# easyeda_schematic.net
KiCad netlist of a schematic drawn in EasyEDA
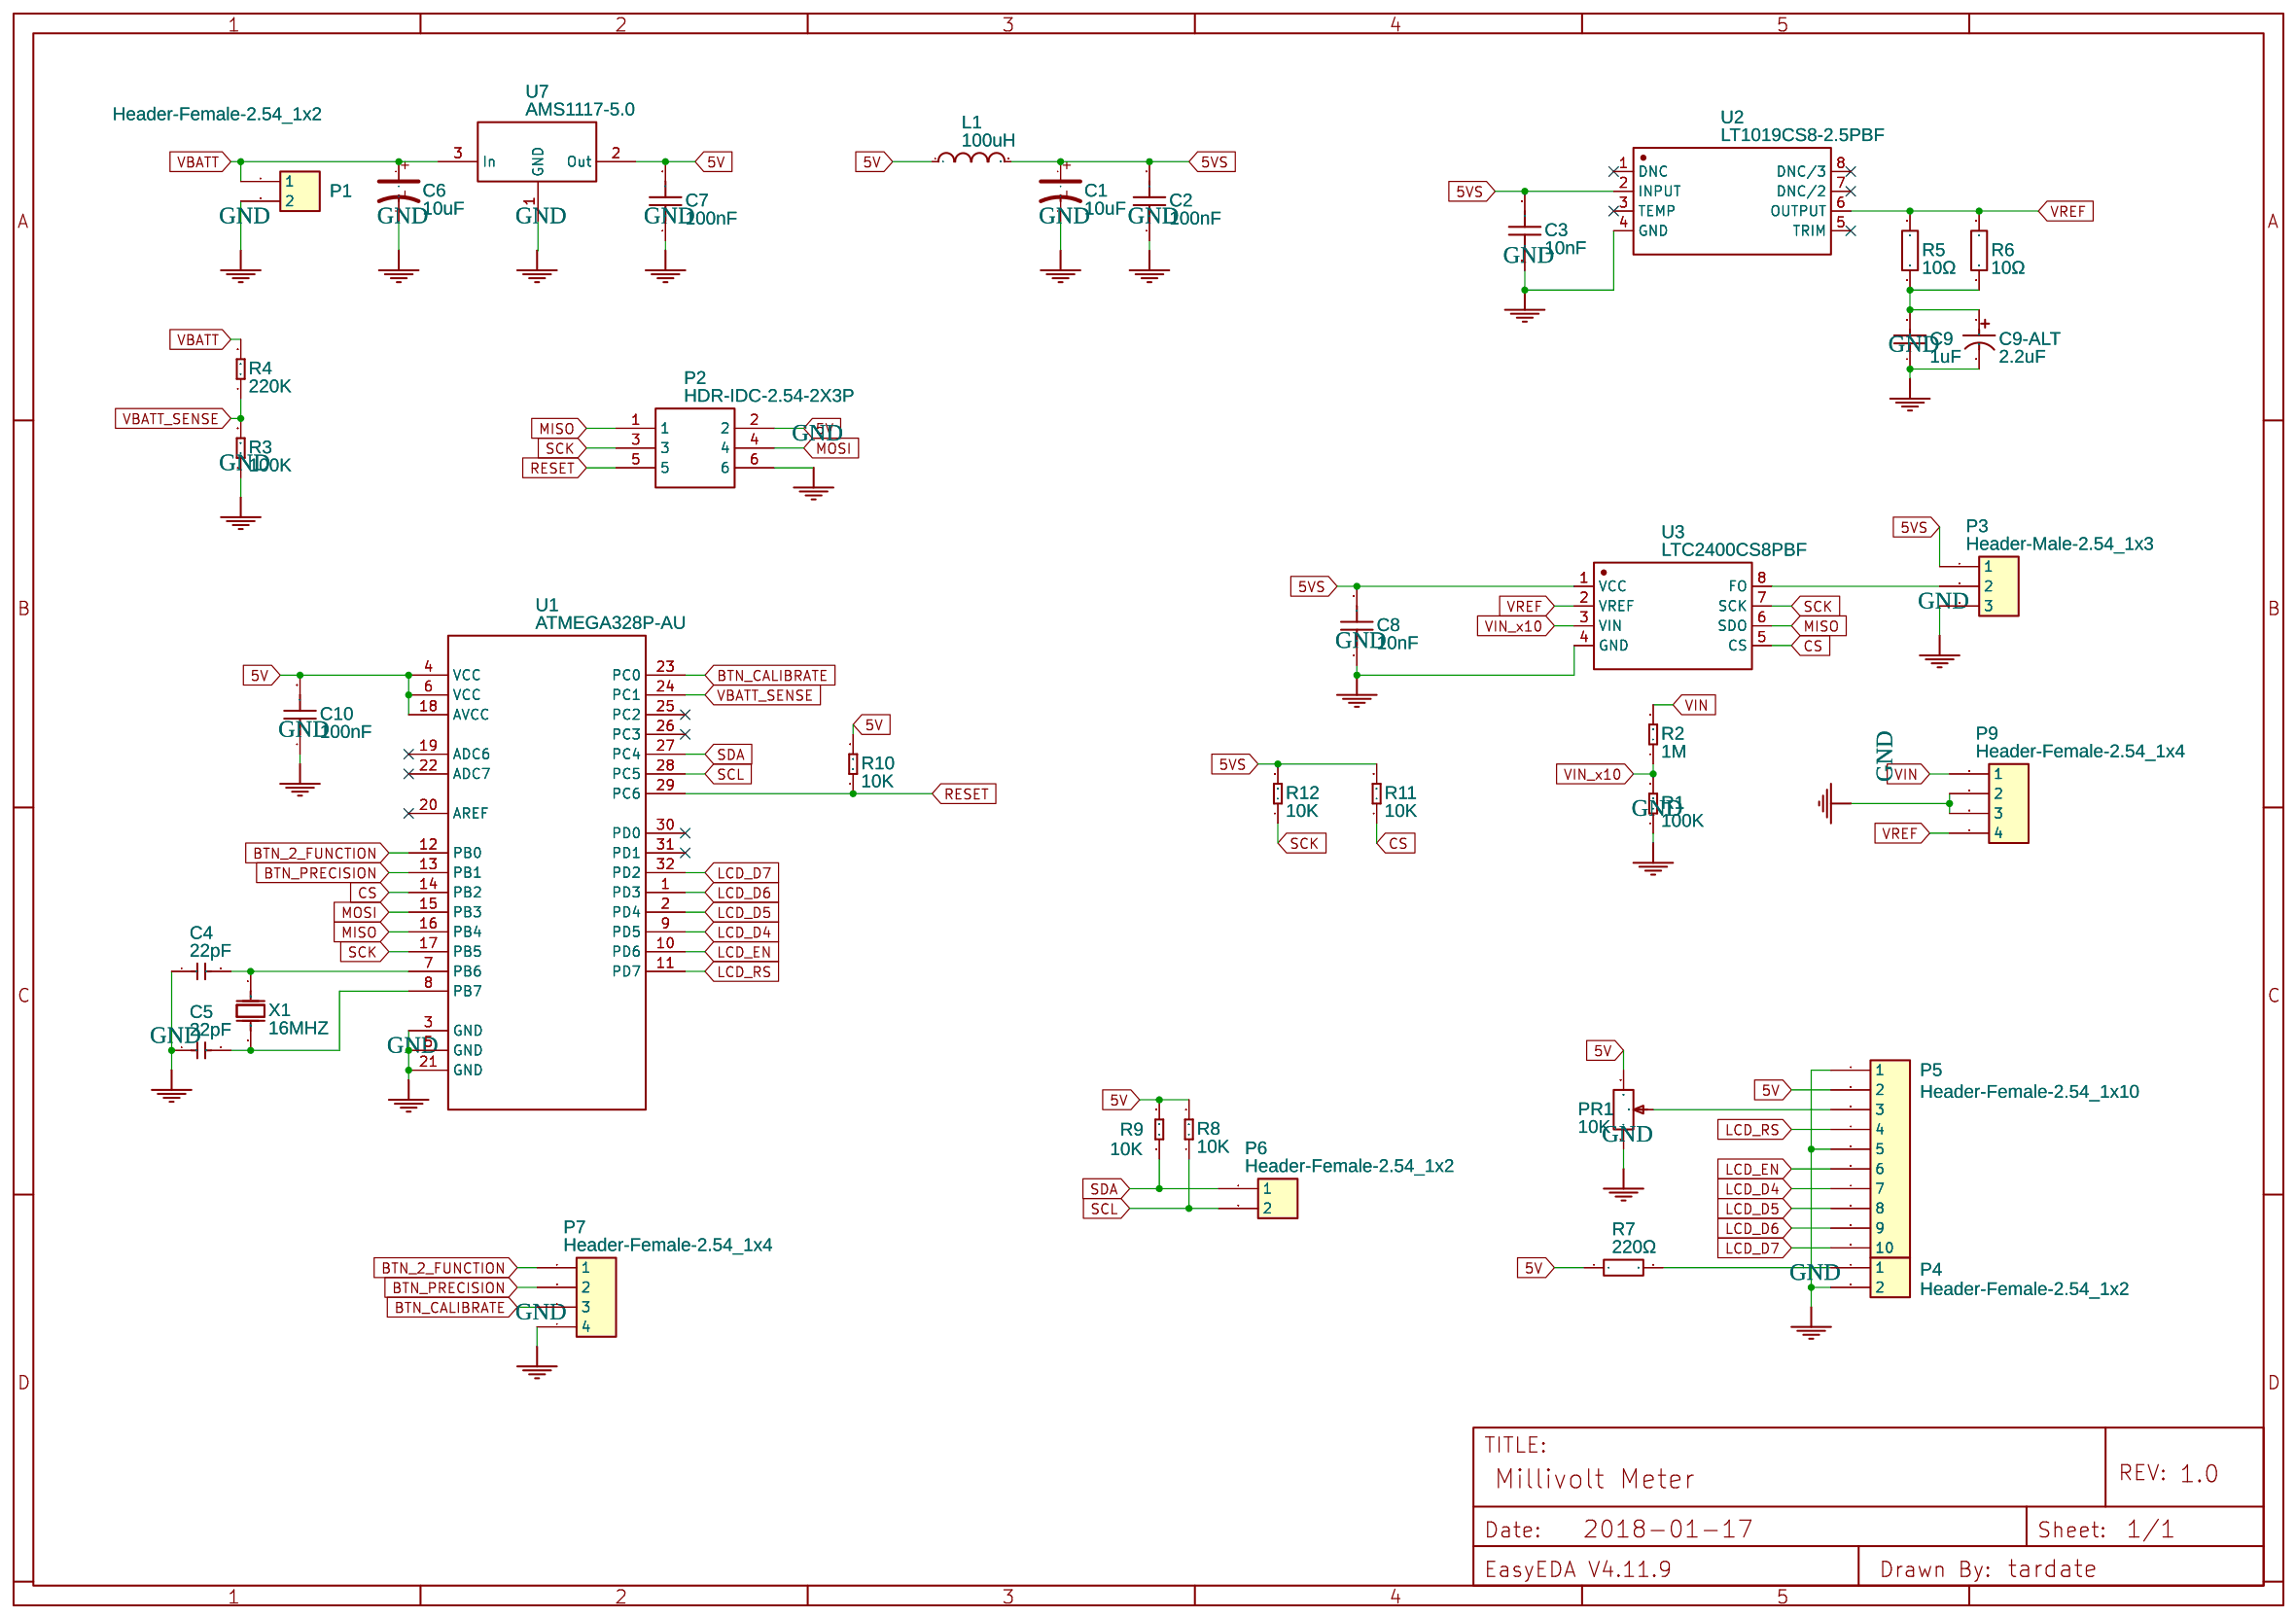
[diagram p0: schematic sheet]

(export (version "E")
  (design (tool "Eeschema 10.0.6"))
  (components
    (comp (ref "C1")
      (value "10uF")
      (fields (field (name "BOM_Manufacturer Part") "UWX1C100MCL1GB"))
      (libsource (lib "") (part "Unknown_530_90"))
    )
    (comp (ref "C2")
      (value "100nF")
      (fields (field (name "BOM_Manufacturer Part") "CC0805JRX7R9BB103"))
      (libsource (lib "") (part "Unknown_575_95"))
    )
    (comp (ref "C3")
      (value "10nF")
      (fields (field (name "BOM_Manufacturer Part") "CC0805KRX7R9BB103"))
      (libsource (lib "") (part "Unknown_765_110"))
    )
    (comp (ref "C4")
      (value "22pF")
      (fields (field (name "BOM_Manufacturer Part") "CC0805JRNPO9BN220"))
      (libsource (lib "") (part "Unknown_95_485"))
    )
    (comp (ref "C5")
      (value "22pF")
      (fields (field (name "BOM_Manufacturer Part") "CC0805JRNPO9BN220"))
      (libsource (lib "") (part "Unknown_95_525"))
    )
    (comp (ref "C6")
      (value "10uF")
      (fields (field (name "BOM_Manufacturer Part") "UWX1C100MCL1GB"))
      (libsource (lib "") (part "Unknown_195_90"))
    )
    (comp (ref "C7")
      (value "100nF")
      (fields (field (name "BOM_Manufacturer Part") "CC0805JRX7R9BB103"))
      (libsource (lib "") (part "Unknown_330_95"))
    )
    (comp (ref "C8")
      (value "10nF")
      (fields (field (name "BOM_Manufacturer Part") "CC0805KRX7R9BB103"))
      (libsource (lib "") (part "Unknown_680_310"))
    )
    (comp (ref "C9")
      (value "1uF")
      (fields (field (name "BOM_Manufacturer Part") "0805B105K500NT"))
      (libsource (lib "") (part "Unknown_960_165"))
    )
    (comp (ref "C9-ALT")
      (value "2.2uF")
      (fields (field (name "BOM_Manufacturer Part") "2.2uF 50V 5*11"))
      (libsource (lib "") (part "Unknown_995_165"))
    )
    (comp (ref "C10")
      (value "100nF")
      (fields (field (name "BOM_Manufacturer Part") "CC0805JRX7R9BB103"))
      (libsource (lib "") (part "Unknown_145_355"))
    )
    (comp (ref "L1")
      (value "100uH")
      (fields (field (name "BOM_Manufacturer Part") "MLF2012C101KT000"))
      (libsource (lib "") (part "Unknown_485_75"))
    )
    (comp (ref "P1") (value "Header-Female-2.54_1x2") (libsource (lib "") (part "Unknown_130_90")))
    (comp (ref "P2") (value "HDR-IDC-2.54-2X3P") (libsource (lib "") (part "Unknown_345_240")))
    (comp (ref "P3") (value "Header-Male-2.54_1x3") (libsource (lib "") (part "Unknown_990_290")))
    (comp (ref "P4") (value "Header-Female-2.54_1x2") (libsource (lib "") (part "Unknown_935_640")))
    (comp (ref "P5") (value "Header-Female-2.54_1x10") (libsource (lib "") (part "Unknown_935_580")))
    (comp (ref "P6") (value "Header-Female-2.54_1x2") (libsource (lib "") (part "Unknown_625_600")))
    (comp (ref "P7") (value "Header-Female-2.54_1x4") (libsource (lib "") (part "Unknown_280_650")))
    (comp (ref "P9") (value "Header-Female-2.54_1x4") (libsource (lib "") (part "Unknown_995_400")))
    (comp (ref "PR1")
      (value "10K")
      (fields (field (name "BOM_Manufacturer Part") "RM065-V1-103"))
      (libsource (lib "") (part "Unknown_820_555"))
    )
    (comp (ref "R1")
      (value "100K")
      (fields (field (name "BOM_Manufacturer Part") "RC0805FR-07100KL"))
      (libsource (lib "") (part "Unknown_830_400"))
    )
    (comp (ref "R2")
      (value "1M")
      (fields (field (name "BOM_Manufacturer Part") "RC0805JR-071ML"))
      (libsource (lib "") (part "Unknown_830_365"))
    )
    (comp (ref "R3")
      (value "100K")
      (fields (field (name "BOM_Manufacturer Part") "RC0805FR-07100KL"))
      (libsource (lib "") (part "Unknown_115_220"))
    )
    (comp (ref "R4")
      (value "220K")
      (fields (field (name "BOM_Manufacturer Part") "RC0603JR-07220KL"))
      (libsource (lib "") (part "Unknown_115_180"))
    )
    (comp (ref "R5")
      (value "10Ω")
      (fields (field (name "BOM_Manufacturer Part") "0805W8J0100T5E"))
      (libsource (lib "") (part "Unknown_960_120"))
    )
    (comp (ref "R6")
      (value "10Ω")
      (fields (field (name "BOM_Manufacturer Part") "0805W8J0100T5E"))
      (libsource (lib "") (part "Unknown_995_120"))
    )
    (comp (ref "R7")
      (value "220Ω")
      (fields (field (name "BOM_Manufacturer Part") "0805W8J0221T5E"))
      (libsource (lib "") (part "Unknown_815_635"))
    )
    (comp (ref "R8")
      (value "10K")
      (fields (field (name "BOM_Manufacturer Part") "RC0805FR-0710KL"))
      (libsource (lib "") (part "Unknown_595_565"))
    )
    (comp (ref "R9")
      (value "10K")
      (fields (field (name "BOM_Manufacturer Part") "RC0805FR-0710KL"))
      (libsource (lib "") (part "Unknown_580_565"))
    )
    (comp (ref "R10")
      (value "10K")
      (fields (field (name "BOM_Manufacturer Part") "RC0805FR-0710KL"))
      (libsource (lib "") (part "Unknown_425_380"))
    )
    (comp (ref "R11")
      (value "10K")
      (fields (field (name "BOM_Manufacturer Part") "RC0805FR-0710KL"))
      (libsource (lib "") (part "Unknown_690_395"))
    )
    (comp (ref "R12")
      (value "10K")
      (fields (field (name "BOM_Manufacturer Part") "RC0805FR-0710KL"))
      (libsource (lib "") (part "Unknown_640_395"))
    )
    (comp (ref "U1") (value "ATMEGA328P-AU") (libsource (lib "") (part "Unknown_270_425")))
    (comp (ref "U2")
      (value "LT1019CS8-2.5PBF")
      (fields (field (name "BOM_Manufacturer Part") "?"))
      (libsource (lib "") (part "Unknown_870_70"))
    )
    (comp (ref "U3")
      (value "LTC2400CS8PBF")
      (fields (field (name "BOM_Manufacturer Part") "?"))
      (libsource (lib "") (part "Unknown_840_280"))
    )
    (comp (ref "U7") (value "AMS1117-5.0") (libsource (lib "") (part "Unknown_265_75")))
    (comp (ref "X1")
      (value "16MHZ")
      (fields (field (name "BOM_Manufacturer Part") "X49SD16MSD2SC"))
      (libsource (lib "") (part "Unknown_120_505"))
    )
  )
  (nets
    (net (code "1") (name "5V") (class "Default")
      (node (ref "C10") (pin "2") (pinfunction "2_2") (pintype "unspecified"))
      (node (ref "C7") (pin "2") (pinfunction "2_2") (pintype "unspecified"))
      (node (ref "L1") (pin "1") (pinfunction "1_1") (pintype "unspecified"))
      (node (ref "P2") (pin "2") (pinfunction "2_2") (pintype "unspecified"))
      (node (ref "P5") (pin "2") (pinfunction "2_2") (pintype "input"))
      (node (ref "PR1") (pin "3") (pinfunction "3_3") (pintype "input"))
      (node (ref "R10") (pin "2") (pinfunction "2_2") (pintype "unspecified"))
      (node (ref "R7") (pin "1") (pinfunction "1_1") (pintype "input"))
      (node (ref "R8") (pin "2") (pinfunction "2_2") (pintype "unspecified"))
      (node (ref "R9") (pin "2") (pinfunction "2_2") (pintype "unspecified"))
      (node (ref "U1") (pin "18") (pinfunction "AVCC_18") (pintype "passive"))
      (node (ref "U1") (pin "4") (pinfunction "VCC_4") (pintype "passive"))
      (node (ref "U1") (pin "6") (pinfunction "VCC_6") (pintype "passive"))
      (node (ref "U7") (pin "2") (pinfunction "Out_2") (pintype "unspecified"))
    )
    (net (code "2") (name "5VS") (class "Default")
      (node (ref "C1") (pin "+") (pinfunction "+_+") (pintype "unspecified"))
      (node (ref "C2") (pin "2") (pinfunction "2_2") (pintype "unspecified"))
      (node (ref "C3") (pin "2") (pinfunction "2_2") (pintype "unspecified"))
      (node (ref "C8") (pin "2") (pinfunction "2_2") (pintype "unspecified"))
      (node (ref "L1") (pin "2") (pinfunction "2_2") (pintype "unspecified"))
      (node (ref "P3") (pin "1") (pinfunction "1_1") (pintype "input"))
      (node (ref "R11") (pin "2") (pinfunction "2_2") (pintype "unspecified"))
      (node (ref "R12") (pin "2") (pinfunction "2_2") (pintype "unspecified"))
      (node (ref "U2") (pin "2") (pinfunction "INPUT_2") (pintype "unspecified"))
      (node (ref "U3") (pin "1") (pinfunction "VCC_1") (pintype "unspecified"))
    )
    (net (code "3") (name "BTN_2_FUNCTION") (class "Default")
      (node (ref "P7") (pin "1") (pinfunction "1_1") (pintype "input"))
      (node (ref "U1") (pin "12") (pinfunction "PB0_12") (pintype "unspecified"))
    )
    (net (code "4") (name "BTN_CALIBRATE") (class "Default")
      (node (ref "P7") (pin "3") (pinfunction "3_3") (pintype "input"))
      (node (ref "U1") (pin "23") (pinfunction "PC0_23") (pintype "unspecified"))
    )
    (net (code "5") (name "BTN_PRECISION") (class "Default")
      (node (ref "P7") (pin "2") (pinfunction "2_2") (pintype "input"))
      (node (ref "U1") (pin "13") (pinfunction "PB1_13") (pintype "unspecified"))
    )
    (net (code "6") (name "CS") (class "Default")
      (node (ref "R11") (pin "1") (pinfunction "1_1") (pintype "unspecified"))
      (node (ref "U1") (pin "14") (pinfunction "PB2_14") (pintype "unspecified"))
      (node (ref "U3") (pin "5") (pinfunction "CS_5") (pintype "unspecified"))
    )
    (net (code "7") (name "GND") (class "Default")
      (node (ref "C1") (pin "-") (pinfunction "-_-") (pintype "unspecified"))
      (node (ref "C10") (pin "1") (pinfunction "1_1") (pintype "unspecified"))
      (node (ref "C2") (pin "1") (pinfunction "1_1") (pintype "unspecified"))
      (node (ref "C3") (pin "1") (pinfunction "1_1") (pintype "unspecified"))
      (node (ref "C4") (pin "1") (pinfunction "1_1") (pintype "unspecified"))
      (node (ref "C5") (pin "1") (pinfunction "1_1") (pintype "unspecified"))
      (node (ref "C6") (pin "-") (pinfunction "-_-") (pintype "unspecified"))
      (node (ref "C7") (pin "1") (pinfunction "1_1") (pintype "unspecified"))
      (node (ref "C8") (pin "1") (pinfunction "1_1") (pintype "unspecified"))
      (node (ref "C9") (pin "1") (pinfunction "1_1") (pintype "input"))
      (node (ref "C9-ALT") (pin "2") (pinfunction "2_2") (pintype "input"))
      (node (ref "P1") (pin "2") (pinfunction "2_2") (pintype "input"))
      (node (ref "P2") (pin "6") (pinfunction "6_6") (pintype "unspecified"))
      (node (ref "P3") (pin "3") (pinfunction "3_3") (pintype "input"))
      (node (ref "P4") (pin "2") (pinfunction "2_2") (pintype "input"))
      (node (ref "P5") (pin "1") (pinfunction "1_1") (pintype "input"))
      (node (ref "P5") (pin "5") (pinfunction "5_5") (pintype "input"))
      (node (ref "P7") (pin "4") (pinfunction "4_4") (pintype "input"))
      (node (ref "P9") (pin "2") (pinfunction "2_2") (pintype "input"))
      (node (ref "P9") (pin "3") (pinfunction "3_3") (pintype "input"))
      (node (ref "PR1") (pin "1") (pinfunction "1_1") (pintype "input"))
      (node (ref "R1") (pin "1") (pinfunction "1_1") (pintype "unspecified"))
      (node (ref "R3") (pin "1") (pinfunction "1_1") (pintype "unspecified"))
      (node (ref "U1") (pin "21") (pinfunction "GND_21") (pintype "unspecified"))
      (node (ref "U1") (pin "3") (pinfunction "GND_3") (pintype "unspecified"))
      (node (ref "U1") (pin "5") (pinfunction "GND_5") (pintype "unspecified"))
      (node (ref "U2") (pin "4") (pinfunction "GND_4") (pintype "unspecified"))
      (node (ref "U3") (pin "4") (pinfunction "GND_4") (pintype "unspecified"))
      (node (ref "U7") (pin "1") (pinfunction "GND_1") (pintype "unspecified"))
    )
    (net (code "8") (name "LCD_D4") (class "Default")
      (node (ref "P5") (pin "7") (pinfunction "7_7") (pintype "input"))
      (node (ref "U1") (pin "9") (pinfunction "PD5_9") (pintype "unspecified"))
    )
    (net (code "9") (name "LCD_D5") (class "Default")
      (node (ref "P5") (pin "8") (pinfunction "8_8") (pintype "input"))
      (node (ref "U1") (pin "2") (pinfunction "PD4_2") (pintype "unspecified"))
    )
    (net (code "10") (name "LCD_D6") (class "Default")
      (node (ref "P5") (pin "9") (pinfunction "9_9") (pintype "input"))
      (node (ref "U1") (pin "1") (pinfunction "PD3_1") (pintype "unspecified"))
    )
    (net (code "11") (name "LCD_D7") (class "Default")
      (node (ref "P5") (pin "10") (pinfunction "10_10") (pintype "input"))
      (node (ref "U1") (pin "32") (pinfunction "PD2_32") (pintype "unspecified"))
    )
    (net (code "12") (name "LCD_EN") (class "Default")
      (node (ref "P5") (pin "6") (pinfunction "6_6") (pintype "input"))
      (node (ref "U1") (pin "10") (pinfunction "PD6_10") (pintype "unspecified"))
    )
    (net (code "13") (name "LCD_RS") (class "Default")
      (node (ref "P5") (pin "4") (pinfunction "4_4") (pintype "input"))
      (node (ref "U1") (pin "11") (pinfunction "PD7_11") (pintype "unspecified"))
    )
    (net (code "14") (name "MISO") (class "Default")
      (node (ref "P2") (pin "1") (pinfunction "1_1") (pintype "unspecified"))
      (node (ref "U1") (pin "16") (pinfunction "PB4_16") (pintype "unspecified"))
      (node (ref "U3") (pin "6") (pinfunction "SDO_6") (pintype "unspecified"))
    )
    (net (code "15") (name "MOSI") (class "Default")
      (node (ref "P2") (pin "4") (pinfunction "4_4") (pintype "unspecified"))
      (node (ref "U1") (pin "15") (pinfunction "PB3_15") (pintype "unspecified"))
    )
    (net (code "16") (name "Net-(C9-ALT-Pad1)") (class "Default")
      (node (ref "C9") (pin "2") (pinfunction "2_2") (pintype "input"))
      (node (ref "C9-ALT") (pin "1") (pinfunction "1_1") (pintype "input"))
      (node (ref "R5") (pin "1") (pinfunction "1_1") (pintype "input"))
      (node (ref "R6") (pin "1") (pinfunction "1_1") (pintype "input"))
    )
    (net (code "17") (name "Net-(P4-Pad1)") (class "Default")
      (node (ref "P4") (pin "1") (pinfunction "1_1") (pintype "input"))
      (node (ref "R7") (pin "2") (pinfunction "2_2") (pintype "input"))
    )
    (net (code "18") (name "Net-(P5-Pad3)") (class "Default")
      (node (ref "P5") (pin "3") (pinfunction "3_3") (pintype "input"))
      (node (ref "PR1") (pin "2") (pinfunction "2_2") (pintype "input"))
    )
    (net (code "19") (name "Net-(U1-PB6)") (class "Default")
      (node (ref "C4") (pin "2") (pinfunction "2_2") (pintype "unspecified"))
      (node (ref "U1") (pin "7") (pinfunction "PB6_7") (pintype "unspecified"))
      (node (ref "X1") (pin "1") (pinfunction "OSC1_1") (pintype "input"))
    )
    (net (code "20") (name "Net-(U1-PB7)") (class "Default")
      (node (ref "C5") (pin "2") (pinfunction "2_2") (pintype "unspecified"))
      (node (ref "U1") (pin "8") (pinfunction "PB7_8") (pintype "unspecified"))
      (node (ref "X1") (pin "2") (pinfunction "OSC2_2") (pintype "input"))
    )
    (net (code "21") (name "Net-(U3-FO)") (class "Default")
      (node (ref "P3") (pin "2") (pinfunction "2_2") (pintype "input"))
      (node (ref "U3") (pin "8") (pinfunction "FO_8") (pintype "unspecified"))
    )
    (net (code "22") (name "RESET") (class "Default")
      (node (ref "P2") (pin "5") (pinfunction "5_5") (pintype "unspecified"))
      (node (ref "R10") (pin "1") (pinfunction "1_1") (pintype "unspecified"))
      (node (ref "U1") (pin "29") (pinfunction "PC6_29") (pintype "unspecified"))
    )
    (net (code "23") (name "SCK") (class "Default")
      (node (ref "P2") (pin "3") (pinfunction "3_3") (pintype "unspecified"))
      (node (ref "R12") (pin "1") (pinfunction "1_1") (pintype "unspecified"))
      (node (ref "U1") (pin "17") (pinfunction "PB5_17") (pintype "unspecified"))
      (node (ref "U3") (pin "7") (pinfunction "SCK_7") (pintype "unspecified"))
    )
    (net (code "24") (name "SCL") (class "Default")
      (node (ref "P6") (pin "2") (pinfunction "2_2") (pintype "input"))
      (node (ref "R8") (pin "1") (pinfunction "1_1") (pintype "unspecified"))
      (node (ref "U1") (pin "28") (pinfunction "PC5_28") (pintype "unspecified"))
    )
    (net (code "25") (name "SDA") (class "Default")
      (node (ref "P6") (pin "1") (pinfunction "1_1") (pintype "input"))
      (node (ref "R9") (pin "1") (pinfunction "1_1") (pintype "unspecified"))
      (node (ref "U1") (pin "27") (pinfunction "PC4_27") (pintype "unspecified"))
    )
    (net (code "26") (name "VBATT") (class "Default")
      (node (ref "C6") (pin "+") (pinfunction "+_+") (pintype "unspecified"))
      (node (ref "P1") (pin "1") (pinfunction "1_1") (pintype "input"))
      (node (ref "R4") (pin "2") (pinfunction "2_2") (pintype "unspecified"))
      (node (ref "U7") (pin "3") (pinfunction "In_3") (pintype "unspecified"))
    )
    (net (code "27") (name "VBATT_SENSE") (class "Default")
      (node (ref "R3") (pin "2") (pinfunction "2_2") (pintype "unspecified"))
      (node (ref "R4") (pin "1") (pinfunction "1_1") (pintype "unspecified"))
      (node (ref "U1") (pin "24") (pinfunction "PC1_24") (pintype "unspecified"))
    )
    (net (code "28") (name "VIN") (class "Default")
      (node (ref "P9") (pin "1") (pinfunction "1_1") (pintype "input"))
      (node (ref "R2") (pin "2") (pinfunction "2_2") (pintype "unspecified"))
    )
    (net (code "29") (name "VIN_x10") (class "Default")
      (node (ref "R1") (pin "2") (pinfunction "2_2") (pintype "unspecified"))
      (node (ref "R2") (pin "1") (pinfunction "1_1") (pintype "unspecified"))
      (node (ref "U3") (pin "3") (pinfunction "VIN_3") (pintype "unspecified"))
    )
    (net (code "30") (name "VREF") (class "Default")
      (node (ref "P9") (pin "4") (pinfunction "4_4") (pintype "input"))
      (node (ref "R5") (pin "2") (pinfunction "2_2") (pintype "input"))
      (node (ref "R6") (pin "2") (pinfunction "2_2") (pintype "input"))
      (node (ref "U2") (pin "6") (pinfunction "OUTPUT_6") (pintype "unspecified"))
      (node (ref "U3") (pin "2") (pinfunction "VREF_2") (pintype "unspecified"))
    )
    (net (code "31") (name "unconnected-(U1-ADC6-Pad19)") (class "Default")
      (node (ref "U1") (pin "19") (pinfunction "ADC6_19") (pintype "input+no_connect"))
    )
    (net (code "32") (name "unconnected-(U1-ADC7-Pad22)") (class "Default")
      (node (ref "U1") (pin "22") (pinfunction "ADC7_22") (pintype "input+no_connect"))
    )
    (net (code "33") (name "unconnected-(U1-AREF-Pad20)") (class "Default")
      (node (ref "U1") (pin "20") (pinfunction "AREF_20") (pintype "input+no_connect"))
    )
    (net (code "34") (name "unconnected-(U1-PC2-Pad25)") (class "Default")
      (node (ref "U1") (pin "25") (pinfunction "PC2_25") (pintype "unspecified+no_connect"))
    )
    (net (code "35") (name "unconnected-(U1-PC3-Pad26)") (class "Default")
      (node (ref "U1") (pin "26") (pinfunction "PC3_26") (pintype "unspecified+no_connect"))
    )
    (net (code "36") (name "unconnected-(U1-PD0-Pad30)") (class "Default")
      (node (ref "U1") (pin "30") (pinfunction "PD0_30") (pintype "unspecified+no_connect"))
    )
    (net (code "37") (name "unconnected-(U1-PD1-Pad31)") (class "Default")
      (node (ref "U1") (pin "31") (pinfunction "PD1_31") (pintype "unspecified+no_connect"))
    )
    (net (code "38") (name "unconnected-(U2-DNC-Pad1)") (class "Default")
      (node (ref "U2") (pin "1") (pinfunction "DNC_1") (pintype "unspecified+no_connect"))
    )
    (net (code "39") (name "unconnected-(U2-DNC{slash}2-Pad7)") (class "Default")
      (node (ref "U2") (pin "7") (pinfunction "DNC/2_7") (pintype "unspecified+no_connect"))
    )
    (net (code "40") (name "unconnected-(U2-DNC{slash}3-Pad8)") (class "Default")
      (node (ref "U2") (pin "8") (pinfunction "DNC/3_8") (pintype "unspecified+no_connect"))
    )
    (net (code "41") (name "unconnected-(U2-TEMP-Pad3)") (class "Default")
      (node (ref "U2") (pin "3") (pinfunction "TEMP_3") (pintype "unspecified+no_connect"))
    )
    (net (code "42") (name "unconnected-(U2-TRIM-Pad5)") (class "Default")
      (node (ref "U2") (pin "5") (pinfunction "TRIM_5") (pintype "unspecified+no_connect"))
    )
  )
)
